# PROC051D_Decoupling_Caps_Reference.net
KiCad netlist of a schematic drawn in Altium Designer
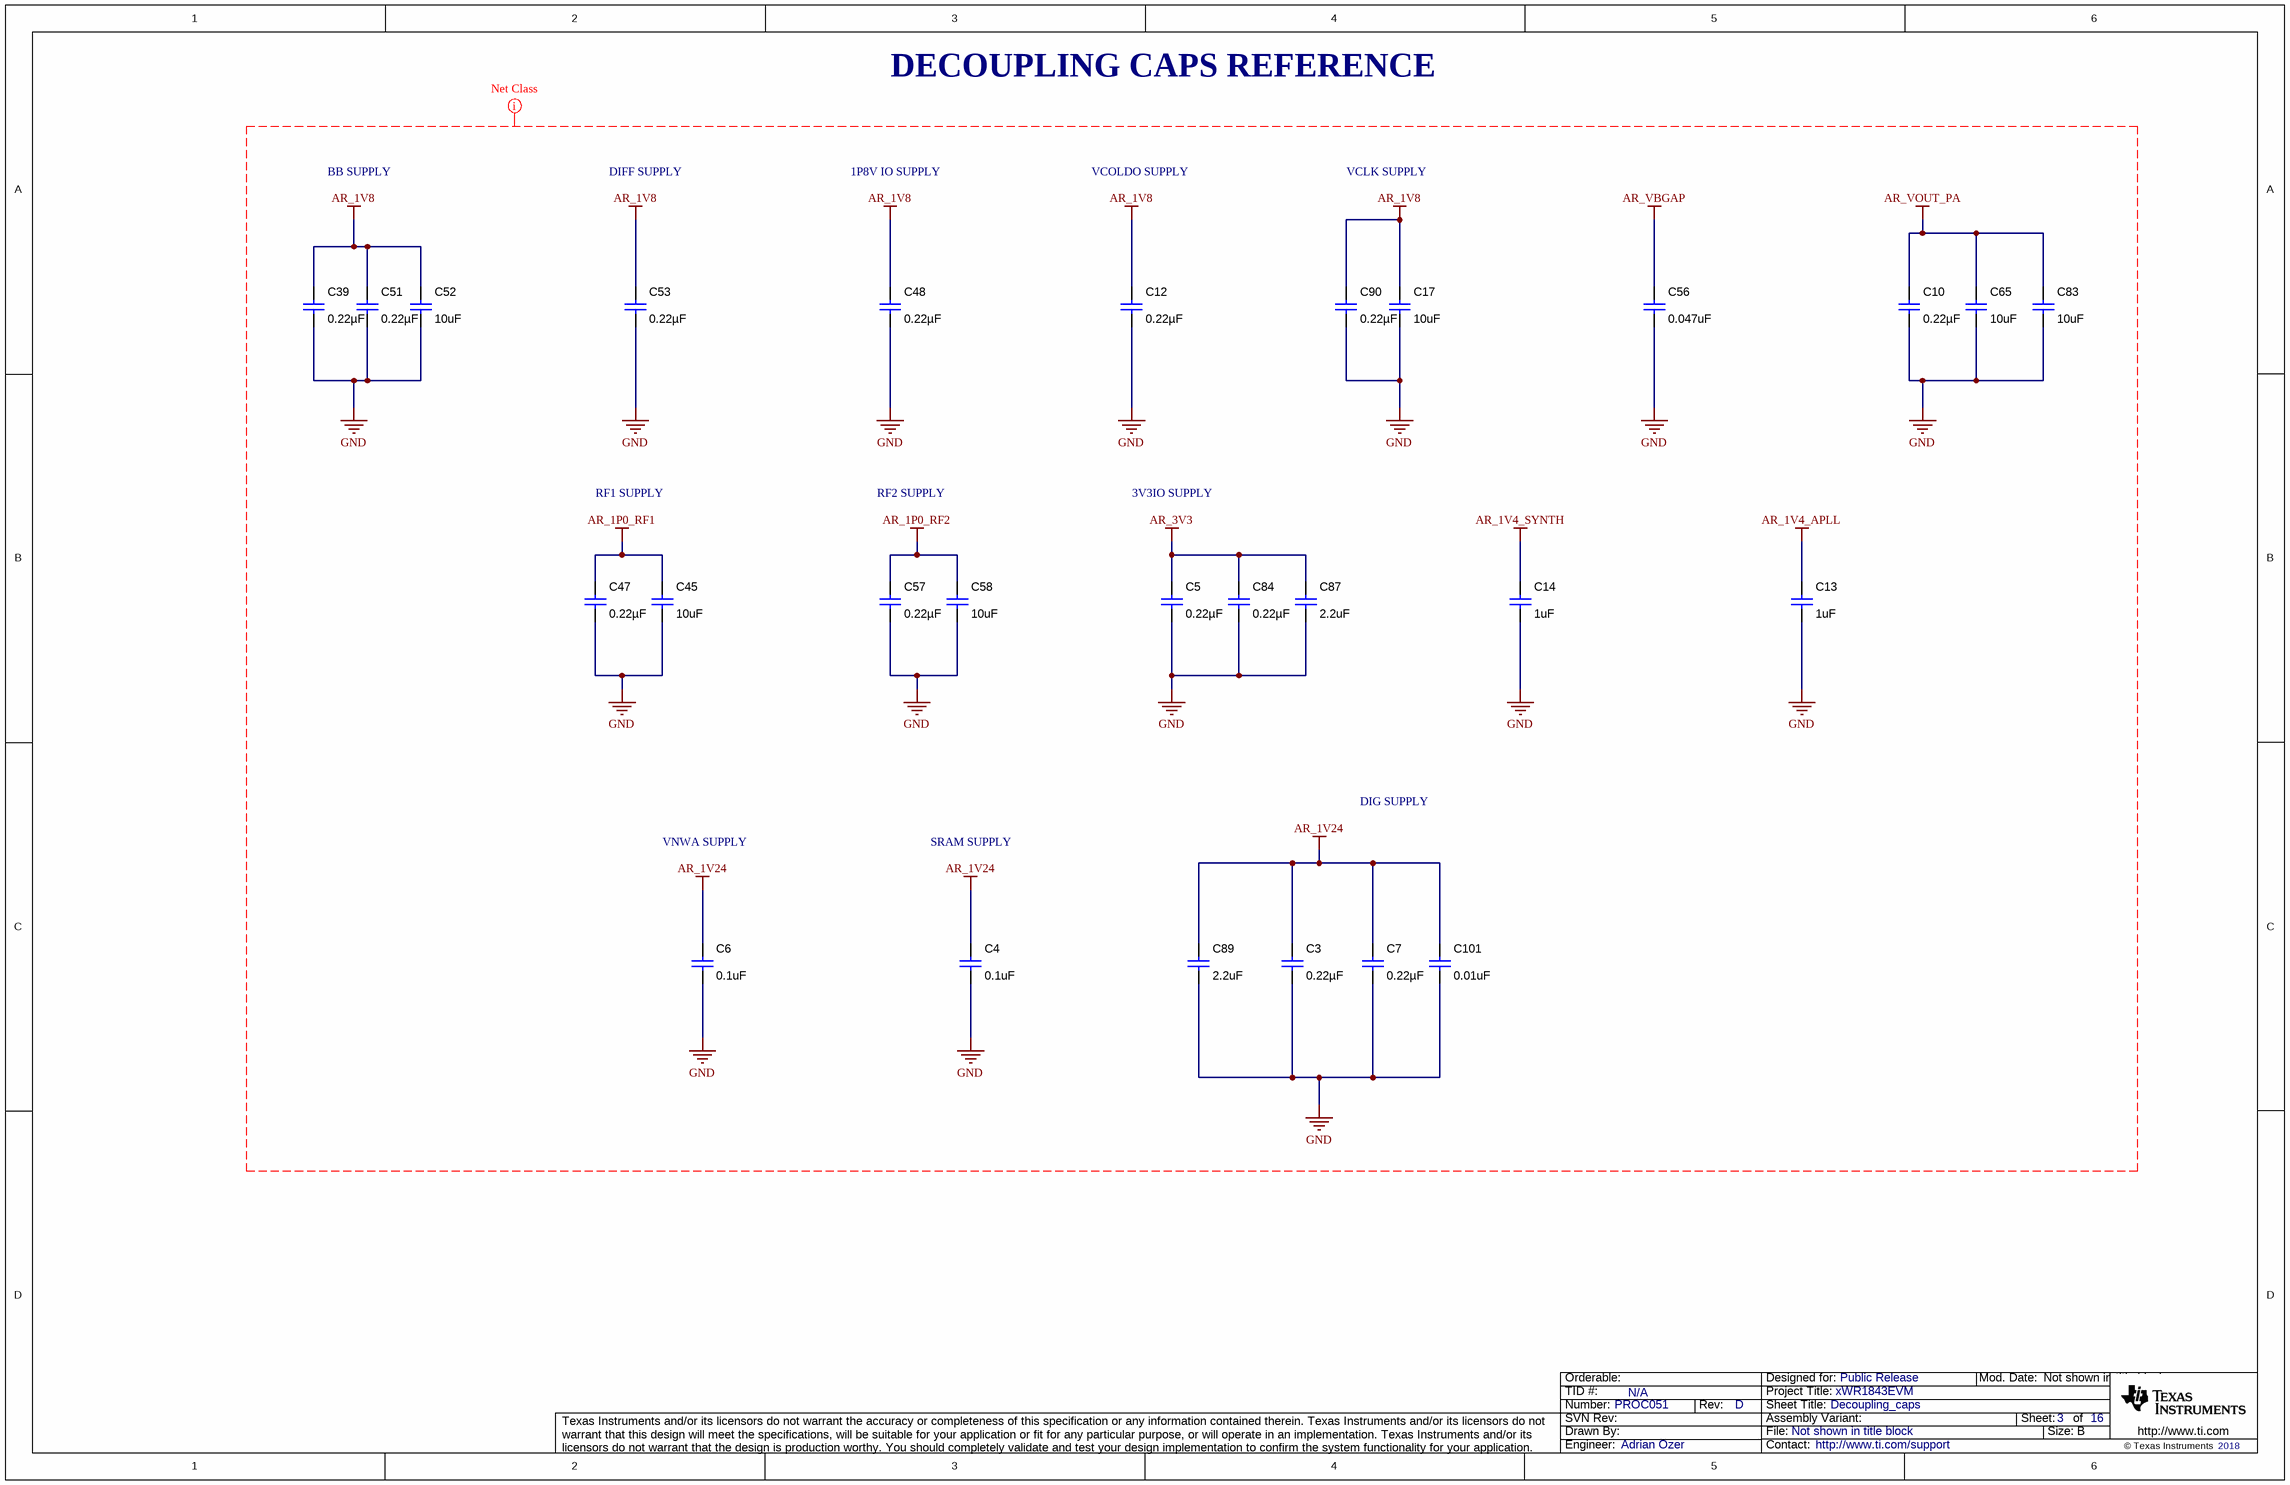
[diagram p0: PROC051D_Decoupling_Caps_Reference.SchDoc]

(export (version "E")
  (design (tool "Eeschema 10.0.6"))
  (components
    (comp (ref "C3")
      (value "GCM155R71C224KE02D")
      (footprint "0402L")
      (description "CAP, CERM, 0.22 µF, 16 V,+/- 10%, X7R, AEC-Q200 Grade 1, 0402")
      (fields (field (name "MANUFACTURER") "MuRata") (field (name "VALUEDISPLAYED") "0.22µF"))
      (libsource (lib "Altium Vault - TI") (part "CMP-0078265-1"))
    )
    (comp (ref "C4")
      (value "GCM155R71C104KA55D")
      (footprint "0402L")
      (description "CAP, CERM, 0.1 uF, 16 V, +/- 10%, X7R, 0402")
      (fields
        (field (name "MANUFACTURER") "MuRata")
        (field (name "VALUEDISPLAYED") "0.1uF")
        (field (name "PUBLISHER") "Texas Instruments")
      )
      (libsource (lib "Altium Vault - TI") (part "CMP-0006351-2"))
    )
    (comp (ref "C5")
      (value "GCM155R71C224KE02D")
      (footprint "0402L")
      (description "CAP, CERM, 0.22 µF, 16 V,+/- 10%, X7R, AEC-Q200 Grade 1, 0402")
      (fields (field (name "MANUFACTURER") "MuRata") (field (name "VALUEDISPLAYED") "0.22µF"))
      (libsource (lib "Altium Vault - TI") (part "CMP-0078265-1"))
    )
    (comp (ref "C6")
      (value "GCM155R71C104KA55D")
      (footprint "0402L")
      (description "CAP, CERM, 0.1 uF, 16 V, +/- 10%, X7R, 0402")
      (fields
        (field (name "MANUFACTURER") "MuRata")
        (field (name "VALUEDISPLAYED") "0.1uF")
        (field (name "PUBLISHER") "Texas Instruments")
      )
      (libsource (lib "Altium Vault - TI") (part "Capacitor"))
    )
    (comp (ref "C7")
      (value "GCM155R71C224KE02D")
      (footprint "0402L")
      (description "CAP, CERM, 0.22 µF, 16 V,+/- 10%, X7R, AEC-Q200 Grade 1, 0402")
      (fields (field (name "MANUFACTURER") "MuRata") (field (name "VALUEDISPLAYED") "0.22µF"))
      (libsource (lib "Altium Vault - TI") (part "CMP-0078265-1"))
    )
    (comp (ref "C10")
      (value "GCM155R71C224KE02D")
      (footprint "0402L")
      (description "CAP, CERM, 0.22 µF, 16 V,+/- 10%, X7R, AEC-Q200 Grade 1, 0402")
      (fields (field (name "MANUFACTURER") "MuRata") (field (name "VALUEDISPLAYED") "0.22µF"))
      (libsource (lib "Altium Vault - TI") (part "CMP-0078265-1"))
    )
    (comp (ref "C12")
      (value "GCM155R71C224KE02D")
      (footprint "0402L")
      (description "CAP, CERM, 0.22 µF, 16 V,+/- 10%, X7R, AEC-Q200 Grade 1, 0402")
      (fields (field (name "MANUFACTURER") "MuRata") (field (name "VALUEDISPLAYED") "0.22µF"))
      (libsource (lib "Altium Vault - TI") (part "CMP-0078265-1"))
    )
    (comp (ref "C13")
      (value "GCM188R71C105KA64D")
      (footprint "0603")
      (description "CAP, CERM, 1 uF, 16 V, +/- 10%, X7R, AEC-Q200 Grade 1, 0603")
      (fields
        (field (name "MANUFACTURER") "MuRata")
        (field (name "VALUEDISPLAYED") "1uF")
        (field (name "PUBLISHER") "Texas Instruments")
      )
      (libsource (lib "Altium Vault - TI") (part "Capacitor"))
    )
    (comp (ref "C14")
      (value "GCM188R71C105KA64D")
      (footprint "0603")
      (description "CAP, CERM, 1 uF, 16 V, +/- 10%, X7R, AEC-Q200 Grade 1, 0603")
      (fields
        (field (name "MANUFACTURER") "MuRata")
        (field (name "VALUEDISPLAYED") "1uF")
        (field (name "PUBLISHER") "Texas Instruments")
      )
      (libsource (lib "Altium Vault - TI") (part "CMP-0007136-5"))
    )
    (comp (ref "C17")
      (value "GCM21BR71A106KE22L")
      (footprint "0805_HV")
      (description "CAP, CERM, 10 uF, 10 V, +/- 10%, X7R, 0805")
      (fields
        (field (name "MANUFACTURER") "MuRata")
        (field (name "VALUEDISPLAYED") "10uF")
        (field (name "PUBLISHER") "Texas Instruments")
      )
      (libsource (lib "Altium Vault - TI") (part "CMP-0008017-2"))
    )
    (comp (ref "C39")
      (value "GCM155R71C224KE02D")
      (footprint "0402L")
      (description "CAP, CERM, 0.22 µF, 16 V,+/- 10%, X7R, AEC-Q200 Grade 1, 0402")
      (fields (field (name "MANUFACTURER") "MuRata") (field (name "VALUEDISPLAYED") "0.22µF"))
      (libsource (lib "Altium Vault - TI") (part "CMP-0078265-1"))
    )
    (comp (ref "C45")
      (value "GCM21BR71A106KE22L")
      (footprint "0805_HV")
      (description "CAP, CERM, 10 uF, 10 V, +/- 10%, X7R, 0805")
      (fields
        (field (name "MANUFACTURER") "MuRata")
        (field (name "VALUEDISPLAYED") "10uF")
        (field (name "PUBLISHER") "Texas Instruments")
      )
      (libsource (lib "Altium Vault - TI") (part "CMP-0008017-2"))
    )
    (comp (ref "C47")
      (value "GCM155R71C224KE02D")
      (footprint "0402L")
      (description "CAP, CERM, 0.22 µF, 16 V,+/- 10%, X7R, AEC-Q200 Grade 1, 0402")
      (fields (field (name "MANUFACTURER") "MuRata") (field (name "VALUEDISPLAYED") "0.22µF"))
      (libsource (lib "Altium Vault - TI") (part "CMP-0078265-1"))
    )
    (comp (ref "C48")
      (value "GCM155R71C224KE02D")
      (footprint "0402L")
      (description "CAP, CERM, 0.22 µF, 16 V,+/- 10%, X7R, AEC-Q200 Grade 1, 0402")
      (fields (field (name "MANUFACTURER") "MuRata") (field (name "VALUEDISPLAYED") "0.22µF"))
      (libsource (lib "Altium Vault - TI") (part "CMP-0078265-1"))
    )
    (comp (ref "C51")
      (value "GCM155R71C224KE02D")
      (footprint "0402L")
      (description "CAP, CERM, 0.22 µF, 16 V,+/- 10%, X7R, AEC-Q200 Grade 1, 0402")
      (fields (field (name "MANUFACTURER") "MuRata") (field (name "VALUEDISPLAYED") "0.22µF"))
      (libsource (lib "Altium Vault - TI") (part "CMP-0078265-1"))
    )
    (comp (ref "C52")
      (value "GCM21BR71A106KE22L")
      (footprint "0805_HV")
      (description "CAP, CERM, 10 uF, 10 V, +/- 10%, X7R, 0805")
      (fields
        (field (name "MANUFACTURER") "MuRata")
        (field (name "VALUEDISPLAYED") "10uF")
        (field (name "PUBLISHER") "Texas Instruments")
      )
      (libsource (lib "Altium Vault - TI") (part "CMP-0008017-2"))
    )
    (comp (ref "C53")
      (value "GCM155R71C224KE02D")
      (footprint "0402L")
      (description "CAP, CERM, 0.22 µF, 16 V,+/- 10%, X7R, AEC-Q200 Grade 1, 0402")
      (fields (field (name "MANUFACTURER") "MuRata") (field (name "VALUEDISPLAYED") "0.22µF"))
      (libsource (lib "Altium Vault - TI") (part "CMP-0078265-1"))
    )
    (comp (ref "C56")
      (value "CGA2B3X7R1H473K050BB")
      (footprint "0402")
      (description "CAP, CERM, 0.047 uF, 50 V, +/- 10%, X7R, AEC-Q200 Grade 1, 0402")
      (fields
        (field (name "MANUFACTURER") "TDK")
        (field (name "VALUEDISPLAYED") "0.047uF")
        (field (name "PUBLISHER") "Texas Instruments")
      )
      (libsource (lib "Altium Vault - TI") (part "Capacitor"))
    )
    (comp (ref "C57")
      (value "GCM155R71C224KE02D")
      (footprint "0402L")
      (description "CAP, CERM, 0.22 µF, 16 V,+/- 10%, X7R, AEC-Q200 Grade 1, 0402")
      (fields (field (name "MANUFACTURER") "MuRata") (field (name "VALUEDISPLAYED") "0.22µF"))
      (libsource (lib "Altium Vault - TI") (part "CMP-0078265-1"))
    )
    (comp (ref "C58")
      (value "GCM21BR71A106KE22L")
      (footprint "0805_HV")
      (description "CAP, CERM, 10 uF, 10 V, +/- 10%, X7R, 0805")
      (fields
        (field (name "MANUFACTURER") "MuRata")
        (field (name "VALUEDISPLAYED") "10uF")
        (field (name "PUBLISHER") "Texas Instruments")
      )
      (libsource (lib "Altium Vault - TI") (part "CMP-0008017-2"))
    )
    (comp (ref "C65")
      (value "GCM21BR71A106KE22L")
      (footprint "0805_HV")
      (description "CAP, CERM, 10 uF, 10 V, +/- 10%, X7R, 0805")
      (fields
        (field (name "MANUFACTURER") "MuRata")
        (field (name "VALUEDISPLAYED") "10uF")
        (field (name "PUBLISHER") "Texas Instruments")
      )
      (libsource (lib "Altium Vault - TI") (part "CMP-0008017-2"))
    )
    (comp (ref "C83")
      (value "GCM21BR71A106KE22L")
      (footprint "0805_HV")
      (description "CAP, CERM, 10 uF, 10 V, +/- 10%, X7R, 0805")
      (fields
        (field (name "MANUFACTURER") "MuRata")
        (field (name "VALUEDISPLAYED") "10uF")
        (field (name "PUBLISHER") "Texas Instruments")
      )
      (libsource (lib "Altium Vault - TI") (part "CMP-0008017-2"))
    )
    (comp (ref "C84")
      (value "GCM155R71C224KE02D")
      (footprint "0402L")
      (description "CAP, CERM, 0.22 µF, 16 V,+/- 10%, X7R, AEC-Q200 Grade 1, 0402")
      (fields (field (name "MANUFACTURER") "MuRata") (field (name "VALUEDISPLAYED") "0.22µF"))
      (libsource (lib "Altium Vault - TI") (part "CMP-0078265-1"))
    )
    (comp (ref "C87")
      (value "GCM188R70J225KE22D")
      (footprint "0603")
      (description "CAP, CERM, 2.2 uF, 6.3 V, +/- 10%, X7R, AEC-Q200 Grade 1, 0603")
      (fields
        (field (name "MANUFACTURER") "MuRata")
        (field (name "VALUEDISPLAYED") "2.2uF")
        (field (name "PUBLISHER") "Texas Instruments")
      )
      (libsource (lib "Altium Vault - TI") (part "Capacitor"))
    )
    (comp (ref "C89")
      (value "GCM188R70J225KE22D")
      (footprint "0603")
      (description "CAP, CERM, 2.2 uF, 6.3 V, +/- 10%, X7R, AEC-Q200 Grade 1, 0603")
      (fields
        (field (name "MANUFACTURER") "MuRata")
        (field (name "VALUEDISPLAYED") "2.2uF")
        (field (name "PUBLISHER") "Texas Instruments")
      )
      (libsource (lib "Altium Vault - TI") (part "Capacitor"))
    )
    (comp (ref "C90")
      (value "GCM155R71C224KE02D")
      (footprint "0402L")
      (description "CAP, CERM, 0.22 µF, 16 V,+/- 10%, X7R, AEC-Q200 Grade 1, 0402")
      (fields (field (name "MANUFACTURER") "MuRata") (field (name "VALUEDISPLAYED") "0.22µF"))
      (libsource (lib "Altium Vault - TI") (part "CMP-0078265-1"))
    )
    (comp (ref "C101")
      (value "GCM155R71E103KA37D")
      (footprint "0402L")
      (description "CAP, CERM, 0.01 uF, 25 V, +/- 10%, X7R, 0402")
      (fields
        (field (name "MANUFACTURER") "MuRata")
        (field (name "VALUEDISPLAYED") "0.01uF")
        (field (name "PUBLISHER") "Texas Instruments")
      )
      (libsource (lib "Altium Vault - TI") (part "CMP-0006352-2"))
    )
  )
  (nets
    (net (code "1") (name "AR_1P0_RF1") (class "Default")
      (node (ref "C45") (pin "2") (pinfunction "2_2") (pintype "passive"))
      (node (ref "C47") (pin "2") (pinfunction "2_2") (pintype "passive"))
    )
    (net (code "2") (name "AR_1P0_RF2") (class "Default")
      (node (ref "C57") (pin "2") (pinfunction "2_2") (pintype "passive"))
      (node (ref "C58") (pin "2") (pinfunction "2_2") (pintype "passive"))
    )
    (net (code "3") (name "AR_1V4_APLL") (class "Default")
      (node (ref "C13") (pin "2") (pinfunction "2_2") (pintype "passive"))
    )
    (net (code "4") (name "AR_1V4_SYNTH") (class "Default")
      (node (ref "C14") (pin "2") (pinfunction "2_2") (pintype "passive"))
    )
    (net (code "5") (name "AR_1V8") (class "Default")
      (node (ref "C12") (pin "2") (pinfunction "2_2") (pintype "passive"))
      (node (ref "C17") (pin "2") (pinfunction "2_2") (pintype "passive"))
      (node (ref "C39") (pin "2") (pinfunction "2_2") (pintype "passive"))
      (node (ref "C48") (pin "2") (pinfunction "2_2") (pintype "passive"))
      (node (ref "C51") (pin "2") (pinfunction "2_2") (pintype "passive"))
      (node (ref "C52") (pin "2") (pinfunction "2_2") (pintype "passive"))
      (node (ref "C53") (pin "2") (pinfunction "2_2") (pintype "passive"))
      (node (ref "C90") (pin "2") (pinfunction "2_2") (pintype "passive"))
    )
    (net (code "6") (name "AR_1V24") (class "Default")
      (node (ref "C101") (pin "1") (pinfunction "1_1") (pintype "passive"))
      (node (ref "C3") (pin "2") (pinfunction "2_2") (pintype "passive"))
      (node (ref "C4") (pin "2") (pinfunction "2_2") (pintype "passive"))
      (node (ref "C6") (pin "2") (pinfunction "2_2") (pintype "passive"))
      (node (ref "C7") (pin "2") (pinfunction "2_2") (pintype "passive"))
      (node (ref "C89") (pin "2") (pinfunction "2_2") (pintype "passive"))
    )
    (net (code "7") (name "AR_3V3") (class "Default")
      (node (ref "C5") (pin "2") (pinfunction "2_2") (pintype "passive"))
      (node (ref "C84") (pin "2") (pinfunction "2_2") (pintype "passive"))
      (node (ref "C87") (pin "2") (pinfunction "2_2") (pintype "passive"))
    )
    (net (code "8") (name "AR_VBGAP") (class "Default")
      (node (ref "C56") (pin "1") (pinfunction "1_1") (pintype "passive"))
    )
    (net (code "9") (name "AR_VOUT_PA") (class "Default")
      (node (ref "C10") (pin "2") (pinfunction "2_2") (pintype "passive"))
      (node (ref "C65") (pin "2") (pinfunction "2_2") (pintype "passive"))
      (node (ref "C83") (pin "2") (pinfunction "2_2") (pintype "passive"))
    )
    (net (code "10") (name "GND") (class "Default")
      (node (ref "C10") (pin "1") (pinfunction "1_1") (pintype "passive"))
      (node (ref "C101") (pin "2") (pinfunction "2_2") (pintype "passive"))
      (node (ref "C12") (pin "1") (pinfunction "1_1") (pintype "passive"))
      (node (ref "C13") (pin "1") (pinfunction "1_1") (pintype "passive"))
      (node (ref "C14") (pin "1") (pinfunction "1_1") (pintype "passive"))
      (node (ref "C17") (pin "1") (pinfunction "1_1") (pintype "passive"))
      (node (ref "C3") (pin "1") (pinfunction "1_1") (pintype "passive"))
      (node (ref "C39") (pin "1") (pinfunction "1_1") (pintype "passive"))
      (node (ref "C4") (pin "1") (pinfunction "1_1") (pintype "passive"))
      (node (ref "C45") (pin "1") (pinfunction "1_1") (pintype "passive"))
      (node (ref "C47") (pin "1") (pinfunction "1_1") (pintype "passive"))
      (node (ref "C48") (pin "1") (pinfunction "1_1") (pintype "passive"))
      (node (ref "C5") (pin "1") (pinfunction "1_1") (pintype "passive"))
      (node (ref "C51") (pin "1") (pinfunction "1_1") (pintype "passive"))
      (node (ref "C52") (pin "1") (pinfunction "1_1") (pintype "passive"))
      (node (ref "C53") (pin "1") (pinfunction "1_1") (pintype "passive"))
      (node (ref "C56") (pin "2") (pinfunction "2_2") (pintype "passive"))
      (node (ref "C57") (pin "1") (pinfunction "1_1") (pintype "passive"))
      (node (ref "C58") (pin "1") (pinfunction "1_1") (pintype "passive"))
      (node (ref "C6") (pin "1") (pinfunction "1_1") (pintype "passive"))
      (node (ref "C65") (pin "1") (pinfunction "1_1") (pintype "passive"))
      (node (ref "C7") (pin "1") (pinfunction "1_1") (pintype "passive"))
      (node (ref "C83") (pin "1") (pinfunction "1_1") (pintype "passive"))
      (node (ref "C84") (pin "1") (pinfunction "1_1") (pintype "passive"))
      (node (ref "C87") (pin "1") (pinfunction "1_1") (pintype "passive"))
      (node (ref "C89") (pin "1") (pinfunction "1_1") (pintype "passive"))
      (node (ref "C90") (pin "1") (pinfunction "1_1") (pintype "passive"))
    )
  )
)
